# Current_sense.net
KiCad netlist of a schematic drawn in EAGLE
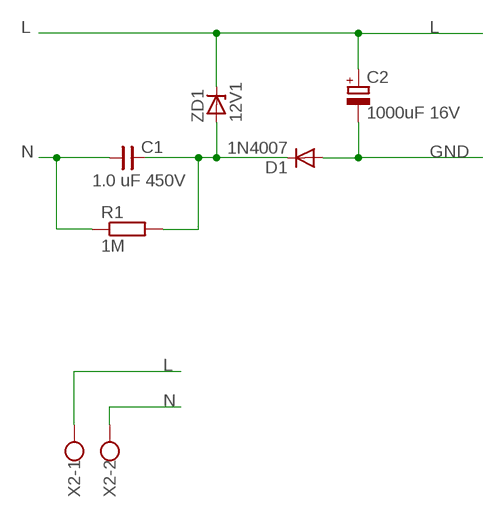
[diagram p0: schematic, sheet 1]
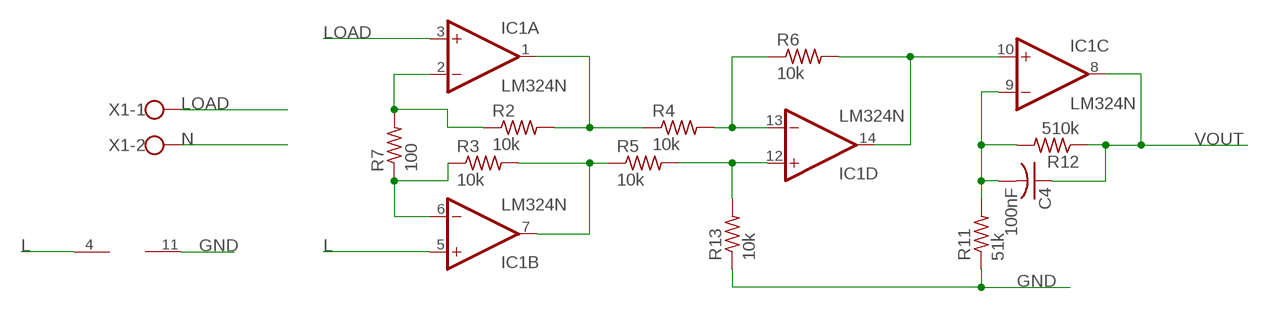
[diagram p1: schematic, sheet 2]

(export (version "E")
  (design (tool "Eeschema 10.0.6"))
  (components
    (comp (ref "C4")
      (value "100nF")
      (footprint "eagle-import:C050-035X075")
      (libsource (lib "eagle-import") (part "C-US050-035X075"))
    )
    (comp (ref "IC1")
      (value "LM324N")
      (footprint "eagle-import:DIL14")
      (libsource (lib "eagle-import") (part "LM324N"))
    )
    (comp (ref "R2")
      (value "10k")
      (footprint "eagle-import:0207_10")
      (libsource (lib "eagle-import") (part "R-US_0207/10"))
    )
    (comp (ref "R3")
      (value "10k")
      (footprint "eagle-import:0207_10")
      (libsource (lib "eagle-import") (part "R-US_0207/10"))
    )
    (comp (ref "R4")
      (value "10k")
      (footprint "eagle-import:0207_10")
      (libsource (lib "eagle-import") (part "R-US_0207/10"))
    )
    (comp (ref "R5")
      (value "10k")
      (footprint "eagle-import:0207_10")
      (libsource (lib "eagle-import") (part "R-US_0207/10"))
    )
    (comp (ref "R6")
      (value "10k")
      (footprint "eagle-import:0207_10")
      (libsource (lib "eagle-import") (part "R-US_0207/10"))
    )
    (comp (ref "R7")
      (value "100")
      (footprint "eagle-import:0207_10")
      (libsource (lib "eagle-import") (part "R-US_0207/10"))
    )
    (comp (ref "R11")
      (value "51k")
      (footprint "eagle-import:0207_10")
      (libsource (lib "eagle-import") (part "R-US_0207/10"))
    )
    (comp (ref "R12")
      (value "510k")
      (footprint "eagle-import:0207_10")
      (libsource (lib "eagle-import") (part "R-US_0207/10"))
    )
    (comp (ref "R13")
      (value "10k")
      (footprint "eagle-import:0207_10")
      (libsource (lib "eagle-import") (part "R-US_0207/10"))
    )
    (comp (ref "X1")
      (value "W237-103")
      (footprint "eagle-import:W237-103")
      (fields (field (name "MPN") "237-103"))
      (libsource (lib "eagle-import") (part "W237-103"))
    )
    (comp (ref "C1")
      (value "1.0 uF 450V")
      (footprint "eagle-import:C150-190X070")
      (libsource (lib "eagle-import") (part "CNP-C150-190X070"))
    )
    (comp (ref "C2")
      (value "1000uF 16V")
      (footprint "eagle-import:E5-8,5")
      (libsource (lib "eagle-import") (part "CPOL-EUE5-8.5"))
    )
    (comp (ref "D1")
      (value "1N4007")
      (footprint "eagle-import:DO41-10")
      (libsource (lib "eagle-import") (part "1N4004"))
    )
    (comp (ref "R1")
      (value "1M")
      (footprint "eagle-import:0207_10")
      (libsource (lib "eagle-import") (part "R-EU_0207/10"))
    )
    (comp (ref "X2")
      (value "W237-102")
      (footprint "eagle-import:W237-102")
      (libsource (lib "eagle-import") (part "W237-102"))
    )
    (comp (ref "ZD1")
      (value "12V1")
      (footprint "eagle-import:DO35Z10")
      (libsource (lib "eagle-import") (part "ZD-DO35Z10"))
    )
  )
  (nets
    (net (code "1") (name "GND") (class "Default")
      (node (ref "C2") (pin "-") (pinfunction "-_-") (pintype "passive"))
      (node (ref "D1") (pin "A") (pinfunction "A_A") (pintype "passive"))
      (node (ref "IC1") (pin "11") (pinfunction "V-_11") (pintype "power_in"))
      (node (ref "R11") (pin "1") (pinfunction "1_1") (pintype "passive"))
      (node (ref "R13") (pin "1") (pinfunction "1_1") (pintype "passive"))
    )
    (net (code "2") (name "L") (class "Default")
      (node (ref "C2") (pin "+") (pinfunction "+_+") (pintype "passive"))
      (node (ref "IC1") (pin "4") (pinfunction "V+_4") (pintype "power_in"))
      (node (ref "IC1") (pin "5") (pinfunction "+IN_5") (pintype "input"))
      (node (ref "X2") (pin "1") (pinfunction "KL_1") (pintype "passive"))
      (node (ref "ZD1") (pin "C") (pinfunction "C_C") (pintype "passive"))
    )
    (net (code "3") (name "LOAD") (class "Default")
      (node (ref "IC1") (pin "3") (pinfunction "+IN_3") (pintype "input"))
      (node (ref "X1") (pin "1") (pinfunction "KL_1") (pintype "passive"))
    )
    (net (code "4") (name "N") (class "Default")
      (node (ref "C1") (pin "1") (pinfunction "1_1") (pintype "passive"))
      (node (ref "R1") (pin "1") (pinfunction "1_1") (pintype "passive"))
      (node (ref "X1") (pin "2") (pinfunction "KL_2") (pintype "passive"))
      (node (ref "X2") (pin "2") (pinfunction "KL_2") (pintype "passive"))
    )
    (net (code "5") (name "Net-(C1-Pad2)") (class "Default")
      (node (ref "C1") (pin "2") (pinfunction "2_2") (pintype "passive"))
      (node (ref "D1") (pin "C") (pinfunction "C_C") (pintype "passive"))
      (node (ref "R1") (pin "2") (pinfunction "2_2") (pintype "passive"))
      (node (ref "ZD1") (pin "A") (pinfunction "A_A") (pintype "passive"))
    )
    (net (code "6") (name "Net-(IC1A--IN)") (class "Default")
      (node (ref "IC1") (pin "2") (pinfunction "-IN_2") (pintype "input"))
      (node (ref "R2") (pin "1") (pinfunction "1_1") (pintype "passive"))
      (node (ref "R7") (pin "2") (pinfunction "2_2") (pintype "passive"))
    )
    (net (code "7") (name "Net-(IC1A-OUT)") (class "Default")
      (node (ref "IC1") (pin "1") (pinfunction "OUT_1") (pintype "output"))
      (node (ref "R2") (pin "2") (pinfunction "2_2") (pintype "passive"))
      (node (ref "R4") (pin "1") (pinfunction "1_1") (pintype "passive"))
    )
    (net (code "8") (name "Net-(IC1B--IN)") (class "Default")
      (node (ref "IC1") (pin "6") (pinfunction "-IN_6") (pintype "input"))
      (node (ref "R3") (pin "1") (pinfunction "1_1") (pintype "passive"))
      (node (ref "R7") (pin "1") (pinfunction "1_1") (pintype "passive"))
    )
    (net (code "9") (name "Net-(IC1B-OUT)") (class "Default")
      (node (ref "IC1") (pin "7") (pinfunction "OUT_7") (pintype "output"))
      (node (ref "R3") (pin "2") (pinfunction "2_2") (pintype "passive"))
      (node (ref "R5") (pin "1") (pinfunction "1_1") (pintype "passive"))
    )
    (net (code "10") (name "Net-(IC1C-+IN)") (class "Default")
      (node (ref "IC1") (pin "10") (pinfunction "+IN_10") (pintype "input"))
      (node (ref "IC1") (pin "14") (pinfunction "OUT_14") (pintype "output"))
      (node (ref "R6") (pin "2") (pinfunction "2_2") (pintype "passive"))
    )
    (net (code "11") (name "Net-(IC1C--IN)") (class "Default")
      (node (ref "C4") (pin "2") (pinfunction "2_2") (pintype "passive"))
      (node (ref "IC1") (pin "9") (pinfunction "-IN_9") (pintype "input"))
      (node (ref "R11") (pin "2") (pinfunction "2_2") (pintype "passive"))
      (node (ref "R12") (pin "2") (pinfunction "2_2") (pintype "passive"))
    )
    (net (code "12") (name "Net-(IC1D-+IN)") (class "Default")
      (node (ref "IC1") (pin "12") (pinfunction "+IN_12") (pintype "input"))
      (node (ref "R13") (pin "2") (pinfunction "2_2") (pintype "passive"))
      (node (ref "R5") (pin "2") (pinfunction "2_2") (pintype "passive"))
    )
    (net (code "13") (name "Net-(IC1D--IN)") (class "Default")
      (node (ref "IC1") (pin "13") (pinfunction "-IN_13") (pintype "input"))
      (node (ref "R4") (pin "2") (pinfunction "2_2") (pintype "passive"))
      (node (ref "R6") (pin "1") (pinfunction "1_1") (pintype "passive"))
    )
    (net (code "14") (name "VOUT") (class "Default")
      (node (ref "C4") (pin "1") (pinfunction "1_1") (pintype "passive"))
      (node (ref "IC1") (pin "8") (pinfunction "OUT_8") (pintype "output"))
      (node (ref "R12") (pin "1") (pinfunction "1_1") (pintype "passive"))
    )
  )
)
